# DP_eDP_Adapter.net
KiCad netlist of a schematic drawn in EAGLE
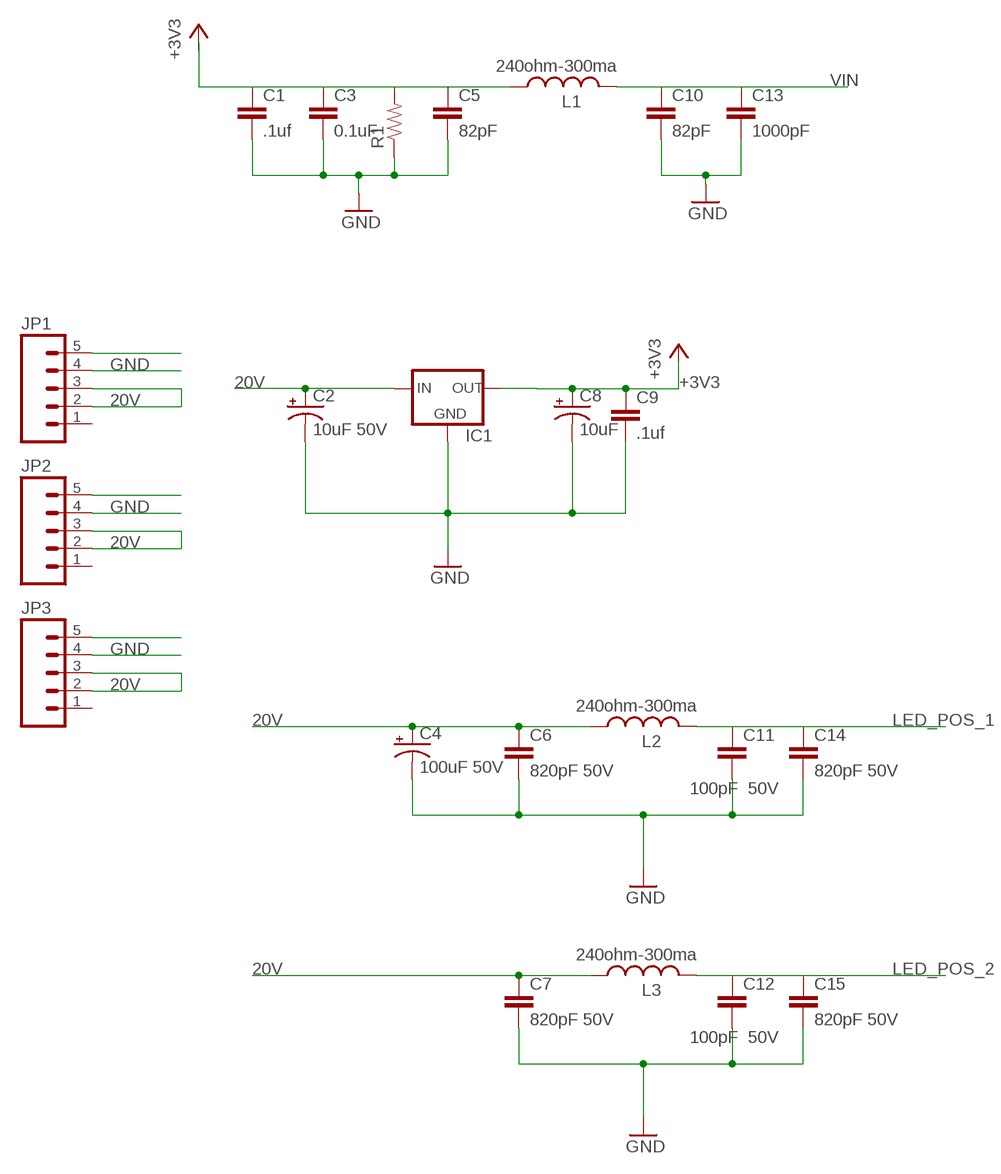
[diagram p0: schematic, sheet 1]
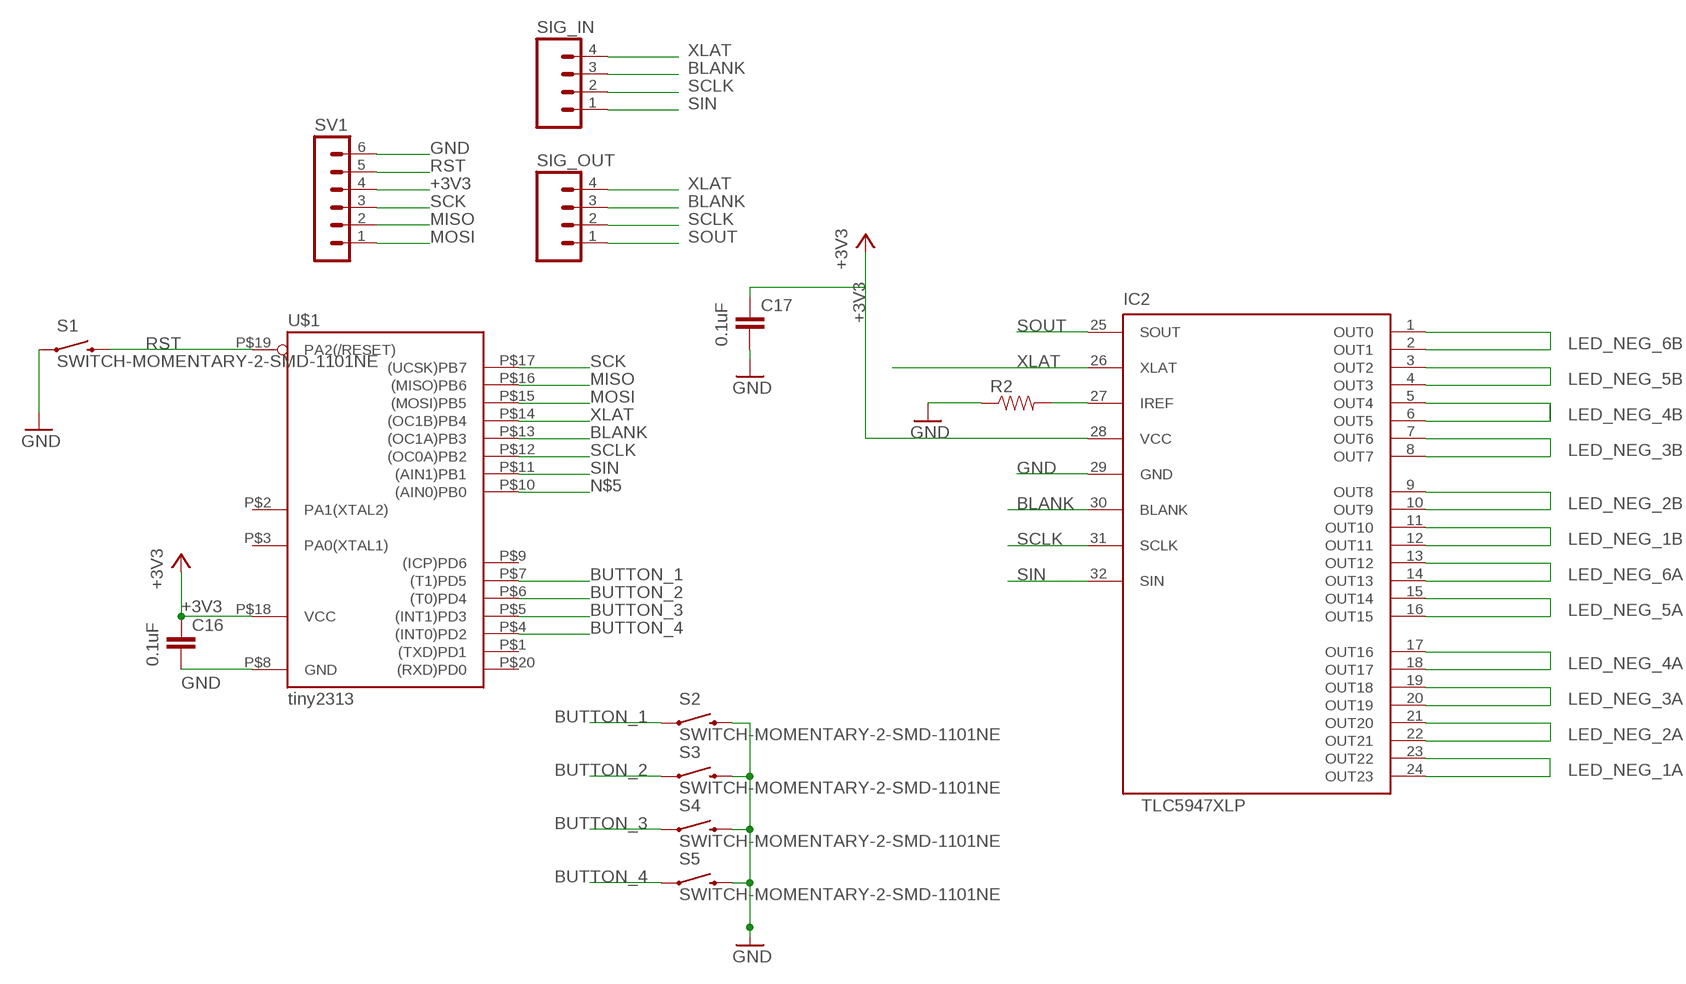
[diagram p1: schematic, sheet 2]
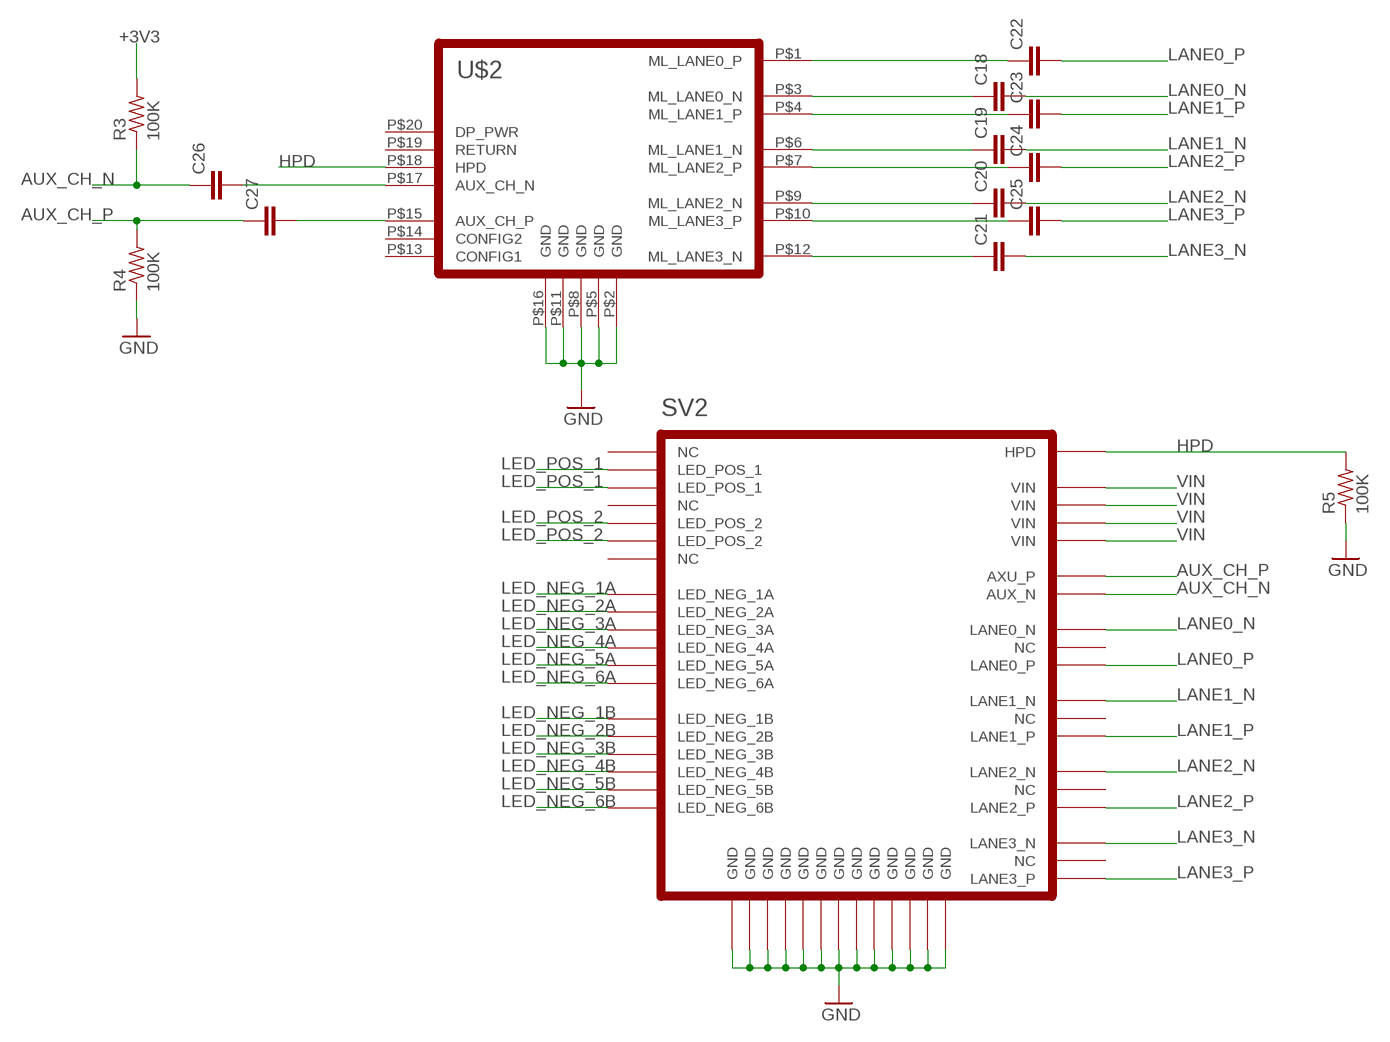
[diagram p2: schematic, sheet 3]

(export (version "E")
  (design (tool "Eeschema 10.0.6"))
  (components
    (comp (ref "C18")
      (value "SPARKFUN-PASSIVES_CAP0402-CAP")
      (footprint "eagle-import:SPARKFUN-PASSIVES_0402-CAP")
      (libsource (lib "eagle-import") (part "SPARKFUN-PASSIVES_CAP0402-CAP"))
    )
    (comp (ref "C19")
      (value "SPARKFUN-PASSIVES_CAP0402-CAP")
      (footprint "eagle-import:SPARKFUN-PASSIVES_0402-CAP")
      (libsource (lib "eagle-import") (part "SPARKFUN-PASSIVES_CAP0402-CAP"))
    )
    (comp (ref "C20")
      (value "SPARKFUN-PASSIVES_CAP0402-CAP")
      (footprint "eagle-import:SPARKFUN-PASSIVES_0402-CAP")
      (libsource (lib "eagle-import") (part "SPARKFUN-PASSIVES_CAP0402-CAP"))
    )
    (comp (ref "C21")
      (value "SPARKFUN-PASSIVES_CAP0402-CAP")
      (footprint "eagle-import:SPARKFUN-PASSIVES_0402-CAP")
      (libsource (lib "eagle-import") (part "SPARKFUN-PASSIVES_CAP0402-CAP"))
    )
    (comp (ref "C22")
      (value "SPARKFUN-PASSIVES_CAP0402-CAP")
      (footprint "eagle-import:SPARKFUN-PASSIVES_0402-CAP")
      (libsource (lib "eagle-import") (part "SPARKFUN-PASSIVES_CAP0402-CAP"))
    )
    (comp (ref "C23")
      (value "SPARKFUN-PASSIVES_CAP0402-CAP")
      (footprint "eagle-import:SPARKFUN-PASSIVES_0402-CAP")
      (libsource (lib "eagle-import") (part "SPARKFUN-PASSIVES_CAP0402-CAP"))
    )
    (comp (ref "C24")
      (value "SPARKFUN-PASSIVES_CAP0402-CAP")
      (footprint "eagle-import:SPARKFUN-PASSIVES_0402-CAP")
      (libsource (lib "eagle-import") (part "SPARKFUN-PASSIVES_CAP0402-CAP"))
    )
    (comp (ref "C25")
      (value "SPARKFUN-PASSIVES_CAP0402-CAP")
      (footprint "eagle-import:SPARKFUN-PASSIVES_0402-CAP")
      (libsource (lib "eagle-import") (part "SPARKFUN-PASSIVES_CAP0402-CAP"))
    )
    (comp (ref "C26")
      (value "SPARKFUN-PASSIVES_CAP0402-CAP")
      (footprint "eagle-import:SPARKFUN-PASSIVES_0402-CAP")
      (libsource (lib "eagle-import") (part "SPARKFUN-PASSIVES_CAP0402-CAP"))
    )
    (comp (ref "C27")
      (value "SPARKFUN-PASSIVES_CAP0402-CAP")
      (footprint "eagle-import:SPARKFUN-PASSIVES_0402-CAP")
      (libsource (lib "eagle-import") (part "SPARKFUN-PASSIVES_CAP0402-CAP"))
    )
    (comp (ref "R3")
      (value "100K")
      (footprint "eagle-import:R0402")
      (libsource (lib "eagle-import") (part "R-US_R0402"))
    )
    (comp (ref "R4")
      (value "100K")
      (footprint "eagle-import:R0402")
      (libsource (lib "eagle-import") (part "R-US_R0402"))
    )
    (comp (ref "R5")
      (value "100K")
      (footprint "eagle-import:R0402")
      (libsource (lib "eagle-import") (part "R-US_R0402"))
    )
    (comp (ref "SV2")
      (value "EDP_CONNECTOR")
      (footprint "eagle-import:EDP_MOLEX")
      (libsource (lib "eagle-import") (part "EDP_CONNECTOR"))
    )
    (comp (ref "U$2")
      (value "DP1RD20JQ2R400")
      (footprint "eagle-import:DP_REVERSE_JAE")
      (libsource (lib "eagle-import") (part "DP1RD20JQ2R400"))
    )
    (comp (ref "C16")
      (value "0.1uF")
      (footprint "eagle-import:0402-CAP")
      (libsource (lib "eagle-import") (part "CAP0402-CAP"))
    )
    (comp (ref "C17")
      (value "0.1uF")
      (footprint "eagle-import:0402-CAP")
      (libsource (lib "eagle-import") (part "CAP0402-CAP"))
    )
    (comp (ref "IC2")
      (value "TLC5947XLP")
      (footprint "eagle-import:QFN32_XLP")
      (libsource (lib "eagle-import") (part "TLC5947XLP"))
    )
    (comp (ref "R2")
      (value "RESISTOR0402-RES")
      (footprint "eagle-import:0402-RES")
      (libsource (lib "eagle-import") (part "RESISTOR0402-RES"))
    )
    (comp (ref "S1")
      (value "SWITCH-MOMENTARY-2-SMD-1101NE")
      (footprint "eagle-import:TACTILE-SWITCH-1101NE")
      (libsource (lib "eagle-import") (part "SWITCH-MOMENTARY-2-SMD-1101NE"))
    )
    (comp (ref "S2")
      (value "SWITCH-MOMENTARY-2-SMD-1101NE")
      (footprint "eagle-import:TACTILE-SWITCH-1101NE")
      (libsource (lib "eagle-import") (part "SWITCH-MOMENTARY-2-SMD-1101NE"))
    )
    (comp (ref "S3")
      (value "SWITCH-MOMENTARY-2-SMD-1101NE")
      (footprint "eagle-import:TACTILE-SWITCH-1101NE")
      (libsource (lib "eagle-import") (part "SWITCH-MOMENTARY-2-SMD-1101NE"))
    )
    (comp (ref "S4")
      (value "SWITCH-MOMENTARY-2-SMD-1101NE")
      (footprint "eagle-import:TACTILE-SWITCH-1101NE")
      (libsource (lib "eagle-import") (part "SWITCH-MOMENTARY-2-SMD-1101NE"))
    )
    (comp (ref "S5")
      (value "SWITCH-MOMENTARY-2-SMD-1101NE")
      (footprint "eagle-import:TACTILE-SWITCH-1101NE")
      (libsource (lib "eagle-import") (part "SWITCH-MOMENTARY-2-SMD-1101NE"))
    )
    (comp (ref "SIG_IN")
      (value "M04PTH")
      (footprint "eagle-import:1X04")
      (libsource (lib "eagle-import") (part "M04PTH"))
    )
    (comp (ref "SIG_OUT")
      (value "M04PTH")
      (footprint "eagle-import:1X04")
      (libsource (lib "eagle-import") (part "M04PTH"))
    )
    (comp (ref "SV1")
      (value "MA06-1")
      (footprint "eagle-import:MA06-1")
      (libsource (lib "eagle-import") (part "MA06-1"))
    )
    (comp (ref "U$1")
      (value "tiny2313")
      (footprint "eagle-import:MLF20")
      (libsource (lib "eagle-import") (part "TINY2313-M"))
    )
    (comp (ref "C1")
      (value ".1uf")
      (footprint "eagle-import:0402-CAP")
      (libsource (lib "eagle-import") (part "SparkFun-Passives_CAP0402-CAP"))
    )
    (comp (ref "C2")
      (value "10uF 50V")
      (footprint "eagle-import:EIA6032")
      (libsource (lib "eagle-import") (part "CAP_POL6032"))
    )
    (comp (ref "C3")
      (value "0.1uF")
      (footprint "eagle-import:0402-CAP")
      (libsource (lib "eagle-import") (part "SparkFun-Passives_CAP0402-CAP"))
    )
    (comp (ref "C4")
      (value "100uF 50V")
      (footprint "eagle-import:EIA6032")
      (libsource (lib "eagle-import") (part "CAP_POL6032"))
    )
    (comp (ref "C5")
      (value "82pF")
      (footprint "eagle-import:0402-CAP")
      (libsource (lib "eagle-import") (part "SparkFun-Passives_CAP0402-CAP"))
    )
    (comp (ref "C6")
      (value "820pF 50V")
      (footprint "eagle-import:0402-CAP")
      (libsource (lib "eagle-import") (part "SparkFun-Passives_CAP0402-CAP"))
    )
    (comp (ref "C7")
      (value "820pF 50V")
      (footprint "eagle-import:0402-CAP")
      (libsource (lib "eagle-import") (part "SparkFun-Passives_CAP0402-CAP"))
    )
    (comp (ref "C8")
      (value "10uF")
      (footprint "eagle-import:EIA6032")
      (libsource (lib "eagle-import") (part "CAP_POL6032"))
    )
    (comp (ref "C9")
      (value ".1uf")
      (footprint "eagle-import:0402-CAP")
      (libsource (lib "eagle-import") (part "SparkFun-Passives_CAP0402-CAP"))
    )
    (comp (ref "C10")
      (value "82pF")
      (footprint "eagle-import:0402-CAP")
      (libsource (lib "eagle-import") (part "SparkFun-Passives_CAP0402-CAP"))
    )
    (comp (ref "C11")
      (value "100pF 50V")
      (footprint "eagle-import:0402-CAP")
      (libsource (lib "eagle-import") (part "SparkFun-Passives_CAP0402-CAP"))
    )
    (comp (ref "C12")
      (value "100pF 50V")
      (footprint "eagle-import:0402-CAP")
      (libsource (lib "eagle-import") (part "SparkFun-Passives_CAP0402-CAP"))
    )
    (comp (ref "C13")
      (value "1000pF")
      (footprint "eagle-import:0402-CAP")
      (libsource (lib "eagle-import") (part "SparkFun-Passives_CAP0402-CAP"))
    )
    (comp (ref "C14")
      (value "820pF 50V")
      (footprint "eagle-import:0402-CAP")
      (libsource (lib "eagle-import") (part "SparkFun-Passives_CAP0402-CAP"))
    )
    (comp (ref "C15")
      (value "820pF 50V")
      (footprint "eagle-import:0402-CAP")
      (libsource (lib "eagle-import") (part "SparkFun-Passives_CAP0402-CAP"))
    )
    (comp (ref "IC1")
      (value "78XXS")
      (footprint "eagle-import:78XXS")
      (libsource (lib "eagle-import") (part "78XXS"))
    )
    (comp (ref "JP1")
      (value "M05PTH")
      (footprint "eagle-import:1X05")
      (libsource (lib "eagle-import") (part "M05PTH"))
    )
    (comp (ref "JP2")
      (value "M05PTH")
      (footprint "eagle-import:1X05")
      (libsource (lib "eagle-import") (part "M05PTH"))
    )
    (comp (ref "JP3")
      (value "M05PTH")
      (footprint "eagle-import:1X05")
      (libsource (lib "eagle-import") (part "M05PTH"))
    )
    (comp (ref "L1")
      (value "240ohm-300ma")
      (footprint "eagle-import:R0402")
      (libsource (lib "eagle-import") (part "L-US"))
    )
    (comp (ref "L2")
      (value "240ohm-300ma")
      (footprint "eagle-import:R0402")
      (libsource (lib "eagle-import") (part "L-US"))
    )
    (comp (ref "L3")
      (value "240ohm-300ma")
      (footprint "eagle-import:R0402")
      (libsource (lib "eagle-import") (part "L-US"))
    )
    (comp (ref "R1")
      (value "RESISTOR0402-RES")
      (footprint "eagle-import:0402-RES")
      (libsource (lib "eagle-import") (part "RESISTOR0402-RES"))
    )
  )
  (nets
    (net (code "1") (name "+3V3") (class "Default")
      (node (ref "C1") (pin "1") (pinfunction "1_1") (pintype "passive"))
      (node (ref "C16") (pin "1") (pinfunction "1_1") (pintype "passive"))
      (node (ref "C17") (pin "1") (pinfunction "1_1") (pintype "passive"))
      (node (ref "C3") (pin "1") (pinfunction "1_1") (pintype "passive"))
      (node (ref "C5") (pin "1") (pinfunction "1_1") (pintype "passive"))
      (node (ref "C8") (pin "P$1") (pinfunction "+_P$1") (pintype "passive"))
      (node (ref "C9") (pin "1") (pinfunction "1_1") (pintype "passive"))
      (node (ref "IC1") (pin "OUT") (pinfunction "OUT_OUT") (pintype "passive"))
      (node (ref "IC2") (pin "28") (pinfunction "VCC_28") (pintype "bidirectional"))
      (node (ref "L1") (pin "1") (pinfunction "1_1") (pintype "passive"))
      (node (ref "R1") (pin "2") (pinfunction "2_2") (pintype "passive"))
      (node (ref "R3") (pin "2") (pinfunction "2_2") (pintype "passive"))
      (node (ref "SV1") (pin "4") (pinfunction "4_4") (pintype "passive"))
      (node (ref "U$1") (pin "P$18") (pinfunction "VCC_P$18") (pintype "power_in"))
    )
    (net (code "2") (name "20V") (class "Default")
      (node (ref "C2") (pin "P$1") (pinfunction "+_P$1") (pintype "passive"))
      (node (ref "C4") (pin "P$1") (pinfunction "+_P$1") (pintype "passive"))
      (node (ref "C6") (pin "1") (pinfunction "1_1") (pintype "passive"))
      (node (ref "C7") (pin "1") (pinfunction "1_1") (pintype "passive"))
      (node (ref "IC1") (pin "IN") (pinfunction "IN_IN") (pintype "input"))
      (node (ref "JP1") (pin "2") (pinfunction "2_2") (pintype "passive"))
      (node (ref "JP1") (pin "3") (pinfunction "3_3") (pintype "passive"))
      (node (ref "JP2") (pin "2") (pinfunction "2_2") (pintype "passive"))
      (node (ref "JP2") (pin "3") (pinfunction "3_3") (pintype "passive"))
      (node (ref "JP3") (pin "2") (pinfunction "2_2") (pintype "passive"))
      (node (ref "JP3") (pin "3") (pinfunction "3_3") (pintype "passive"))
      (node (ref "L2") (pin "1") (pinfunction "1_1") (pintype "passive"))
      (node (ref "L3") (pin "1") (pinfunction "1_1") (pintype "passive"))
    )
    (net (code "3") (name "AUX_CH_N") (class "Default")
      (node (ref "C26") (pin "1") (pinfunction "1_1") (pintype "passive"))
      (node (ref "R3") (pin "1") (pinfunction "1_1") (pintype "passive"))
      (node (ref "SV2") (pin "P$10") (pinfunction "AUX_N_P$10") (pintype "bidirectional"))
    )
    (net (code "4") (name "AUX_CH_P") (class "Default")
      (node (ref "C27") (pin "1") (pinfunction "1_1") (pintype "passive"))
      (node (ref "R4") (pin "2") (pinfunction "2_2") (pintype "passive"))
      (node (ref "SV2") (pin "P$9") (pinfunction "AXU_P_P$9") (pintype "bidirectional"))
    )
    (net (code "5") (name "BLANK") (class "Default")
      (node (ref "IC2") (pin "30") (pinfunction "BLANK_30") (pintype "bidirectional"))
      (node (ref "SIG_IN") (pin "3") (pinfunction "3_3") (pintype "passive"))
      (node (ref "SIG_OUT") (pin "3") (pinfunction "3_3") (pintype "passive"))
      (node (ref "U$1") (pin "P$13") (pinfunction "(OC1A)PB3_P$13") (pintype "bidirectional"))
    )
    (net (code "6") (name "BUTTON_1") (class "Default")
      (node (ref "S2") (pin "P$1") (pinfunction "1_P$1") (pintype "passive"))
      (node (ref "U$1") (pin "P$7") (pinfunction "(T1)PD5_P$7") (pintype "bidirectional"))
    )
    (net (code "7") (name "BUTTON_2") (class "Default")
      (node (ref "S3") (pin "P$1") (pinfunction "1_P$1") (pintype "passive"))
      (node (ref "U$1") (pin "P$6") (pinfunction "(T0)PD4_P$6") (pintype "bidirectional"))
    )
    (net (code "8") (name "BUTTON_3") (class "Default")
      (node (ref "S4") (pin "P$1") (pinfunction "1_P$1") (pintype "passive"))
      (node (ref "U$1") (pin "P$5") (pinfunction "(INT1)PD3_P$5") (pintype "bidirectional"))
    )
    (net (code "9") (name "BUTTON_4") (class "Default")
      (node (ref "S5") (pin "P$1") (pinfunction "1_P$1") (pintype "passive"))
      (node (ref "U$1") (pin "P$4") (pinfunction "(INT0)PD2_P$4") (pintype "bidirectional"))
    )
    (net (code "10") (name "GND") (class "Default")
      (node (ref "C1") (pin "2") (pinfunction "2_2") (pintype "passive"))
      (node (ref "C10") (pin "2") (pinfunction "2_2") (pintype "passive"))
      (node (ref "C11") (pin "2") (pinfunction "2_2") (pintype "passive"))
      (node (ref "C12") (pin "2") (pinfunction "2_2") (pintype "passive"))
      (node (ref "C13") (pin "2") (pinfunction "2_2") (pintype "passive"))
      (node (ref "C14") (pin "2") (pinfunction "2_2") (pintype "passive"))
      (node (ref "C15") (pin "2") (pinfunction "2_2") (pintype "passive"))
      (node (ref "C16") (pin "2") (pinfunction "2_2") (pintype "passive"))
      (node (ref "C17") (pin "2") (pinfunction "2_2") (pintype "passive"))
      (node (ref "C2") (pin "P$2") (pinfunction "-_P$2") (pintype "passive"))
      (node (ref "C3") (pin "2") (pinfunction "2_2") (pintype "passive"))
      (node (ref "C4") (pin "P$2") (pinfunction "-_P$2") (pintype "passive"))
      (node (ref "C5") (pin "2") (pinfunction "2_2") (pintype "passive"))
      (node (ref "C6") (pin "2") (pinfunction "2_2") (pintype "passive"))
      (node (ref "C7") (pin "2") (pinfunction "2_2") (pintype "passive"))
      (node (ref "C8") (pin "P$2") (pinfunction "-_P$2") (pintype "passive"))
      (node (ref "C9") (pin "2") (pinfunction "2_2") (pintype "passive"))
      (node (ref "IC1") (pin "GND") (pinfunction "GND_GND") (pintype "input"))
      (node (ref "IC2") (pin "29") (pinfunction "GND_29") (pintype "bidirectional"))
      (node (ref "JP1") (pin "4") (pinfunction "4_4") (pintype "passive"))
      (node (ref "JP1") (pin "5") (pinfunction "5_5") (pintype "passive"))
      (node (ref "JP2") (pin "4") (pinfunction "4_4") (pintype "passive"))
      (node (ref "JP2") (pin "5") (pinfunction "5_5") (pintype "passive"))
      (node (ref "JP3") (pin "4") (pinfunction "4_4") (pintype "passive"))
      (node (ref "JP3") (pin "5") (pinfunction "5_5") (pintype "passive"))
      (node (ref "R1") (pin "1") (pinfunction "1_1") (pintype "passive"))
      (node (ref "R2") (pin "1") (pinfunction "1_1") (pintype "passive"))
      (node (ref "R4") (pin "1") (pinfunction "1_1") (pintype "passive"))
      (node (ref "R5") (pin "1") (pinfunction "1_1") (pintype "passive"))
      (node (ref "S1") (pin "P$1") (pinfunction "1_P$1") (pintype "passive"))
      (node (ref "S2") (pin "P$2") (pinfunction "2_P$2") (pintype "passive"))
      (node (ref "S3") (pin "P$2") (pinfunction "2_P$2") (pintype "passive"))
      (node (ref "S4") (pin "P$2") (pinfunction "2_P$2") (pintype "passive"))
      (node (ref "S5") (pin "P$2") (pinfunction "2_P$2") (pintype "passive"))
      (node (ref "SV1") (pin "6") (pinfunction "6_6") (pintype "passive"))
      (node (ref "SV2") (pin "P$1") (pinfunction "GND_P$1") (pintype "bidirectional"))
      (node (ref "SV2") (pin "P$11") (pinfunction "GND_P$11") (pintype "bidirectional"))
      (node (ref "SV2") (pin "P$15") (pinfunction "GND_P$15") (pintype "bidirectional"))
      (node (ref "SV2") (pin "P$19") (pinfunction "GND_P$19") (pintype "bidirectional"))
      (node (ref "SV2") (pin "P$23") (pinfunction "GND_P$23") (pintype "bidirectional"))
      (node (ref "SV2") (pin "P$27") (pinfunction "GND_P$27") (pintype "bidirectional"))
      (node (ref "SV2") (pin "P$28") (pinfunction "GND_P$28") (pintype "bidirectional"))
      (node (ref "SV2") (pin "P$29") (pinfunction "GND_P$29") (pintype "bidirectional"))
      (node (ref "SV2") (pin "P$3") (pinfunction "GND_P$3") (pintype "bidirectional"))
      (node (ref "SV2") (pin "P$36") (pinfunction "GND_P$36") (pintype "bidirectional"))
      (node (ref "SV2") (pin "P$43") (pinfunction "GND_P$43") (pintype "bidirectional"))
      (node (ref "SV2") (pin "P$51") (pinfunction "GND_P$51") (pintype "bidirectional"))
      (node (ref "SV2") (pin "P$8") (pinfunction "GND_P$8") (pintype "bidirectional"))
      (node (ref "U$1") (pin "P$8") (pinfunction "GND_P$8") (pintype "power_in"))
      (node (ref "U$2") (pin "P$11") (pinfunction "GND_P$11") (pintype "bidirectional"))
      (node (ref "U$2") (pin "P$16") (pinfunction "GND_P$16") (pintype "bidirectional"))
      (node (ref "U$2") (pin "P$2") (pinfunction "GND_P$2") (pintype "bidirectional"))
      (node (ref "U$2") (pin "P$5") (pinfunction "GND_P$5") (pintype "bidirectional"))
      (node (ref "U$2") (pin "P$8") (pinfunction "GND_P$8") (pintype "bidirectional"))
    )
    (net (code "11") (name "HPD") (class "Default")
      (node (ref "R5") (pin "2") (pinfunction "2_2") (pintype "passive"))
      (node (ref "SV2") (pin "P$2") (pinfunction "HPD_P$2") (pintype "bidirectional"))
      (node (ref "U$2") (pin "P$18") (pinfunction "HPD_P$18") (pintype "bidirectional"))
    )
    (net (code "12") (name "LANE0_N") (class "Default")
      (node (ref "C18") (pin "2") (pinfunction "2_2") (pintype "passive"))
      (node (ref "SV2") (pin "P$12") (pinfunction "LANE0_N_P$12") (pintype "bidirectional"))
    )
    (net (code "13") (name "LANE0_P") (class "Default")
      (node (ref "C22") (pin "2") (pinfunction "2_2") (pintype "passive"))
      (node (ref "SV2") (pin "P$14") (pinfunction "LANE0_P_P$14") (pintype "bidirectional"))
    )
    (net (code "14") (name "LANE1_N") (class "Default")
      (node (ref "C19") (pin "2") (pinfunction "2_2") (pintype "passive"))
      (node (ref "SV2") (pin "P$16") (pinfunction "LANE1_N_P$16") (pintype "bidirectional"))
    )
    (net (code "15") (name "LANE1_P") (class "Default")
      (node (ref "C23") (pin "2") (pinfunction "2_2") (pintype "passive"))
      (node (ref "SV2") (pin "P$18") (pinfunction "LANE1_P_P$18") (pintype "bidirectional"))
    )
    (net (code "16") (name "LANE2_N") (class "Default")
      (node (ref "C20") (pin "2") (pinfunction "2_2") (pintype "passive"))
      (node (ref "SV2") (pin "P$20") (pinfunction "LANE2_N_P$20") (pintype "bidirectional"))
    )
    (net (code "17") (name "LANE2_P") (class "Default")
      (node (ref "C24") (pin "2") (pinfunction "2_2") (pintype "passive"))
      (node (ref "SV2") (pin "P$22") (pinfunction "LANE2_P_P$22") (pintype "bidirectional"))
    )
    (net (code "18") (name "LANE3_N") (class "Default")
      (node (ref "C21") (pin "2") (pinfunction "2_2") (pintype "passive"))
      (node (ref "SV2") (pin "P$24") (pinfunction "LANE3_N_P$24") (pintype "bidirectional"))
    )
    (net (code "19") (name "LANE3_P") (class "Default")
      (node (ref "C25") (pin "2") (pinfunction "2_2") (pintype "passive"))
      (node (ref "SV2") (pin "P$26") (pinfunction "LANE3_P_P$26") (pintype "bidirectional"))
    )
    (net (code "20") (name "LED_NEG_1A") (class "Default")
      (node (ref "IC2") (pin "23") (pinfunction "OUT22_23") (pintype "bidirectional"))
      (node (ref "IC2") (pin "24") (pinfunction "OUT23_24") (pintype "bidirectional"))
      (node (ref "SV2") (pin "P$42") (pinfunction "LED_NEG_1A_P$42") (pintype "bidirectional"))
    )
    (net (code "21") (name "LED_NEG_1B") (class "Default")
      (node (ref "IC2") (pin "11") (pinfunction "OUT10_11") (pintype "bidirectional"))
      (node (ref "IC2") (pin "12") (pinfunction "OUT11_12") (pintype "bidirectional"))
      (node (ref "SV2") (pin "P$35") (pinfunction "LED_NEG_1B_P$35") (pintype "bidirectional"))
    )
    (net (code "22") (name "LED_NEG_2A") (class "Default")
      (node (ref "IC2") (pin "21") (pinfunction "OUT20_21") (pintype "bidirectional"))
      (node (ref "IC2") (pin "22") (pinfunction "OUT21_22") (pintype "bidirectional"))
      (node (ref "SV2") (pin "P$41") (pinfunction "LED_NEG_2A_P$41") (pintype "bidirectional"))
    )
    (net (code "23") (name "LED_NEG_2B") (class "Default")
      (node (ref "IC2") (pin "10") (pinfunction "OUT9_10") (pintype "bidirectional"))
      (node (ref "IC2") (pin "9") (pinfunction "OUT8_9") (pintype "bidirectional"))
      (node (ref "SV2") (pin "P$34") (pinfunction "LED_NEG_2B_P$34") (pintype "bidirectional"))
    )
    (net (code "24") (name "LED_NEG_3A") (class "Default")
      (node (ref "IC2") (pin "19") (pinfunction "OUT18_19") (pintype "bidirectional"))
      (node (ref "IC2") (pin "20") (pinfunction "OUT19_20") (pintype "bidirectional"))
      (node (ref "SV2") (pin "P$40") (pinfunction "LED_NEG_3A_P$40") (pintype "bidirectional"))
    )
    (net (code "25") (name "LED_NEG_3B") (class "Default")
      (node (ref "IC2") (pin "7") (pinfunction "OUT6_7") (pintype "bidirectional"))
      (node (ref "IC2") (pin "8") (pinfunction "OUT7_8") (pintype "bidirectional"))
      (node (ref "SV2") (pin "P$33") (pinfunction "LED_NEG_3B_P$33") (pintype "bidirectional"))
    )
    (net (code "26") (name "LED_NEG_4A") (class "Default")
      (node (ref "IC2") (pin "17") (pinfunction "OUT16_17") (pintype "bidirectional"))
      (node (ref "IC2") (pin "18") (pinfunction "OUT17_18") (pintype "bidirectional"))
      (node (ref "SV2") (pin "P$39") (pinfunction "LED_NEG_4A_P$39") (pintype "bidirectional"))
    )
    (net (code "27") (name "LED_NEG_4B") (class "Default")
      (node (ref "IC2") (pin "5") (pinfunction "OUT4_5") (pintype "bidirectional"))
      (node (ref "IC2") (pin "6") (pinfunction "OUT5_6") (pintype "bidirectional"))
      (node (ref "SV2") (pin "P$32") (pinfunction "LED_NEG_4B_P$32") (pintype "bidirectional"))
    )
    (net (code "28") (name "LED_NEG_5A") (class "Default")
      (node (ref "IC2") (pin "15") (pinfunction "OUT14_15") (pintype "bidirectional"))
      (node (ref "IC2") (pin "16") (pinfunction "OUT15_16") (pintype "bidirectional"))
      (node (ref "SV2") (pin "P$38") (pinfunction "LED_NEG_5A_P$38") (pintype "bidirectional"))
    )
    (net (code "29") (name "LED_NEG_5B") (class "Default")
      (node (ref "IC2") (pin "3") (pinfunction "OUT2_3") (pintype "bidirectional"))
      (node (ref "IC2") (pin "4") (pinfunction "OUT3_4") (pintype "bidirectional"))
      (node (ref "SV2") (pin "P$31") (pinfunction "LED_NEG_5B_P$31") (pintype "bidirectional"))
    )
    (net (code "30") (name "LED_NEG_6A") (class "Default")
      (node (ref "IC2") (pin "13") (pinfunction "OUT12_13") (pintype "bidirectional"))
      (node (ref "IC2") (pin "14") (pinfunction "OUT13_14") (pintype "bidirectional"))
      (node (ref "SV2") (pin "P$37") (pinfunction "LED_NEG_6A_P$37") (pintype "bidirectional"))
    )
    (net (code "31") (name "LED_NEG_6B") (class "Default")
      (node (ref "IC2") (pin "1") (pinfunction "OUT0_1") (pintype "bidirectional"))
      (node (ref "IC2") (pin "2") (pinfunction "OUT1_2") (pintype "bidirectional"))
      (node (ref "SV2") (pin "P$30") (pinfunction "LED_NEG_6B_P$30") (pintype "bidirectional"))
    )
    (net (code "32") (name "LED_POS_1") (class "Default")
      (node (ref "C11") (pin "1") (pinfunction "1_1") (pintype "passive"))
      (node (ref "C14") (pin "1") (pinfunction "1_1") (pintype "passive"))
      (node (ref "L2") (pin "2") (pinfunction "2_2") (pintype "passive"))
      (node (ref "SV2") (pin "P$48") (pinfunction "LED_POS_1_P$48") (pintype "bidirectional"))
      (node (ref "SV2") (pin "P$49") (pinfunction "LED_POS_1_P$49") (pintype "bidirectional"))
    )
    (net (code "33") (name "LED_POS_2") (class "Default")
      (node (ref "C12") (pin "1") (pinfunction "1_1") (pintype "passive"))
      (node (ref "C15") (pin "1") (pinfunction "1_1") (pintype "passive"))
      (node (ref "L3") (pin "2") (pinfunction "2_2") (pintype "passive"))
      (node (ref "SV2") (pin "P$45") (pinfunction "LED_POS_2_P$45") (pintype "bidirectional"))
      (node (ref "SV2") (pin "P$46") (pinfunction "LED_POS_2_P$46") (pintype "bidirectional"))
    )
    (net (code "34") (name "MISO") (class "Default")
      (node (ref "SV1") (pin "2") (pinfunction "2_2") (pintype "passive"))
      (node (ref "U$1") (pin "P$16") (pinfunction "(MISO)PB6_P$16") (pintype "bidirectional"))
    )
    (net (code "35") (name "MOSI") (class "Default")
      (node (ref "SV1") (pin "1") (pinfunction "1_1") (pintype "passive"))
      (node (ref "U$1") (pin "P$15") (pinfunction "(MOSI)PB5_P$15") (pintype "bidirectional"))
    )
    (net (code "36") (name "N$5") (class "Default")
      (node (ref "U$1") (pin "P$10") (pinfunction "(AIN0)PB0_P$10") (pintype "bidirectional"))
    )
    (net (code "37") (name "Net-(IC2-IREF)") (class "Default")
      (node (ref "IC2") (pin "27") (pinfunction "IREF_27") (pintype "bidirectional"))
      (node (ref "R2") (pin "2") (pinfunction "2_2") (pintype "passive"))
    )
    (net (code "38") (name "Net-(U$2-AUX_CH_N)") (class "Default")
      (node (ref "C26") (pin "2") (pinfunction "2_2") (pintype "passive"))
      (node (ref "U$2") (pin "P$17") (pinfunction "AUX_CH_N_P$17") (pintype "bidirectional"))
    )
    (net (code "39") (name "Net-(U$2-AUX_CH_P)") (class "Default")
      (node (ref "C27") (pin "2") (pinfunction "2_2") (pintype "passive"))
      (node (ref "U$2") (pin "P$15") (pinfunction "AUX_CH_P_P$15") (pintype "bidirectional"))
    )
    (net (code "40") (name "Net-(U$2-ML_LANE0_N)") (class "Default")
      (node (ref "C18") (pin "1") (pinfunction "1_1") (pintype "passive"))
      (node (ref "U$2") (pin "P$3") (pinfunction "ML_LANE0_N_P$3") (pintype "bidirectional"))
    )
    (net (code "41") (name "Net-(U$2-ML_LANE0_P)") (class "Default")
      (node (ref "C22") (pin "1") (pinfunction "1_1") (pintype "passive"))
      (node (ref "U$2") (pin "P$1") (pinfunction "ML_LANE0_P_P$1") (pintype "bidirectional"))
    )
    (net (code "42") (name "Net-(U$2-ML_LANE1_N)") (class "Default")
      (node (ref "C19") (pin "1") (pinfunction "1_1") (pintype "passive"))
      (node (ref "U$2") (pin "P$6") (pinfunction "ML_LANE1_N_P$6") (pintype "bidirectional"))
    )
    (net (code "43") (name "Net-(U$2-ML_LANE1_P)") (class "Default")
      (node (ref "C23") (pin "1") (pinfunction "1_1") (pintype "passive"))
      (node (ref "U$2") (pin "P$4") (pinfunction "ML_LANE1_P_P$4") (pintype "bidirectional"))
    )
    (net (code "44") (name "Net-(U$2-ML_LANE2_N)") (class "Default")
      (node (ref "C20") (pin "1") (pinfunction "1_1") (pintype "passive"))
      (node (ref "U$2") (pin "P$9") (pinfunction "ML_LANE2_N_P$9") (pintype "bidirectional"))
    )
    (net (code "45") (name "Net-(U$2-ML_LANE2_P)") (class "Default")
      (node (ref "C24") (pin "1") (pinfunction "1_1") (pintype "passive"))
      (node (ref "U$2") (pin "P$7") (pinfunction "ML_LANE2_P_P$7") (pintype "bidirectional"))
    )
    (net (code "46") (name "Net-(U$2-ML_LANE3_N)") (class "Default")
      (node (ref "C21") (pin "1") (pinfunction "1_1") (pintype "passive"))
      (node (ref "U$2") (pin "P$12") (pinfunction "ML_LANE3_N_P$12") (pintype "bidirectional"))
    )
    (net (code "47") (name "Net-(U$2-ML_LANE3_P)") (class "Default")
      (node (ref "C25") (pin "1") (pinfunction "1_1") (pintype "passive"))
      (node (ref "U$2") (pin "P$10") (pinfunction "ML_LANE3_P_P$10") (pintype "bidirectional"))
    )
    (net (code "48") (name "RST") (class "Default")
      (node (ref "S1") (pin "P$2") (pinfunction "2_P$2") (pintype "passive"))
      (node (ref "SV1") (pin "5") (pinfunction "5_5") (pintype "passive"))
      (node (ref "U$1") (pin "P$19") (pinfunction "PA2(/RESET)_P$19") (pintype "input"))
    )
    (net (code "49") (name "SCK") (class "Default")
      (node (ref "SV1") (pin "3") (pinfunction "3_3") (pintype "passive"))
      (node (ref "U$1") (pin "P$17") (pinfunction "(UCSK)PB7_P$17") (pintype "bidirectional"))
    )
    (net (code "50") (name "SCLK") (class "Default")
      (node (ref "IC2") (pin "31") (pinfunction "SCLK_31") (pintype "bidirectional"))
      (node (ref "SIG_IN") (pin "2") (pinfunction "2_2") (pintype "passive"))
      (node (ref "SIG_OUT") (pin "2") (pinfunction "2_2") (pintype "passive"))
      (node (ref "U$1") (pin "P$12") (pinfunction "(OC0A)PB2_P$12") (pintype "bidirectional"))
    )
    (net (code "51") (name "SIN") (class "Default")
      (node (ref "IC2") (pin "32") (pinfunction "SIN_32") (pintype "bidirectional"))
      (node (ref "SIG_IN") (pin "1") (pinfunction "1_1") (pintype "passive"))
      (node (ref "U$1") (pin "P$11") (pinfunction "(AIN1)PB1_P$11") (pintype "bidirectional"))
    )
    (net (code "52") (name "SOUT") (class "Default")
      (node (ref "IC2") (pin "25") (pinfunction "SOUT_25") (pintype "bidirectional"))
      (node (ref "SIG_OUT") (pin "1") (pinfunction "1_1") (pintype "passive"))
    )
    (net (code "53") (name "VIN") (class "Default")
      (node (ref "C10") (pin "1") (pinfunction "1_1") (pintype "passive"))
      (node (ref "C13") (pin "1") (pinfunction "1_1") (pintype "passive"))
      (node (ref "L1") (pin "2") (pinfunction "2_2") (pintype "passive"))
      (node (ref "SV2") (pin "P$4") (pinfunction "VIN_P$4") (pintype "bidirectional"))
      (node (ref "SV2") (pin "P$5") (pinfunction "VIN_P$5") (pintype "bidirectional"))
      (node (ref "SV2") (pin "P$6") (pinfunction "VIN_P$6") (pintype "bidirectional"))
      (node (ref "SV2") (pin "P$7") (pinfunction "VIN_P$7") (pintype "bidirectional"))
    )
    (net (code "54") (name "XLAT") (class "Default")
      (node (ref "IC2") (pin "26") (pinfunction "XLAT_26") (pintype "bidirectional"))
      (node (ref "SIG_IN") (pin "4") (pinfunction "4_4") (pintype "passive"))
      (node (ref "SIG_OUT") (pin "4") (pinfunction "4_4") (pintype "passive"))
      (node (ref "U$1") (pin "P$14") (pinfunction "(OC1B)PB4_P$14") (pintype "bidirectional"))
    )
    (net (code "55") (name "unconnected-(JP1-Pad1)") (class "Default")
      (node (ref "JP1") (pin "1") (pinfunction "1_1") (pintype "passive"))
    )
    (net (code "56") (name "unconnected-(JP2-Pad1)") (class "Default")
      (node (ref "JP2") (pin "1") (pinfunction "1_1") (pintype "passive"))
    )
    (net (code "57") (name "unconnected-(JP3-Pad1)") (class "Default")
      (node (ref "JP3") (pin "1") (pinfunction "1_1") (pintype "passive"))
    )
    (net (code "58") (name "unconnected-(SV2-NC-PadP$13)") (class "Default")
      (node (ref "SV2") (pin "P$13") (pinfunction "NC_P$13") (pintype "bidirectional"))
    )
    (net (code "59") (name "unconnected-(SV2-NC-PadP$17)") (class "Default")
      (node (ref "SV2") (pin "P$17") (pinfunction "NC_P$17") (pintype "bidirectional"))
    )
    (net (code "60") (name "unconnected-(SV2-NC-PadP$21)") (class "Default")
      (node (ref "SV2") (pin "P$21") (pinfunction "NC_P$21") (pintype "bidirectional"))
    )
    (net (code "61") (name "unconnected-(SV2-NC-PadP$25)") (class "Default")
      (node (ref "SV2") (pin "P$25") (pinfunction "NC_P$25") (pintype "bidirectional"))
    )
    (net (code "62") (name "unconnected-(SV2-NC-PadP$44)") (class "Default")
      (node (ref "SV2") (pin "P$44") (pinfunction "NC_P$44") (pintype "bidirectional"))
    )
    (net (code "63") (name "unconnected-(SV2-NC-PadP$47)") (class "Default")
      (node (ref "SV2") (pin "P$47") (pinfunction "NC_P$47") (pintype "bidirectional"))
    )
    (net (code "64") (name "unconnected-(SV2-NC-PadP$50)") (class "Default")
      (node (ref "SV2") (pin "P$50") (pinfunction "NC_P$50") (pintype "bidirectional"))
    )
    (net (code "65") (name "unconnected-(U$1-(ICP)PD6-PadP$9)") (class "Default")
      (node (ref "U$1") (pin "P$9") (pinfunction "(ICP)PD6_P$9") (pintype "bidirectional"))
    )
    (net (code "66") (name "unconnected-(U$1-(RXD)PD0-PadP$20)") (class "Default")
      (node (ref "U$1") (pin "P$20") (pinfunction "(RXD)PD0_P$20") (pintype "bidirectional"))
    )
    (net (code "67") (name "unconnected-(U$1-(TXD)PD1-PadP$1)") (class "Default")
      (node (ref "U$1") (pin "P$1") (pinfunction "(TXD)PD1_P$1") (pintype "bidirectional"))
    )
    (net (code "68") (name "unconnected-(U$1-PA0(XTAL1)-PadP$3)") (class "Default")
      (node (ref "U$1") (pin "P$3") (pinfunction "PA0(XTAL1)_P$3") (pintype "bidirectional"))
    )
    (net (code "69") (name "unconnected-(U$1-PA1(XTAL2)-PadP$2)") (class "Default")
      (node (ref "U$1") (pin "P$2") (pinfunction "PA1(XTAL2)_P$2") (pintype "bidirectional"))
    )
    (net (code "70") (name "unconnected-(U$2-CONFIG1-PadP$13)") (class "Default")
      (node (ref "U$2") (pin "P$13") (pinfunction "CONFIG1_P$13") (pintype "bidirectional"))
    )
    (net (code "71") (name "unconnected-(U$2-CONFIG2-PadP$14)") (class "Default")
      (node (ref "U$2") (pin "P$14") (pinfunction "CONFIG2_P$14") (pintype "bidirectional"))
    )
    (net (code "72") (name "unconnected-(U$2-DP_PWR-PadP$20)") (class "Default")
      (node (ref "U$2") (pin "P$20") (pinfunction "DP_PWR_P$20") (pintype "bidirectional"))
    )
    (net (code "73") (name "unconnected-(U$2-RETURN-PadP$19)") (class "Default")
      (node (ref "U$2") (pin "P$19") (pinfunction "RETURN_P$19") (pintype "bidirectional"))
    )
  )
)
